# rf-remote.net
KiCad netlist of a schematic drawn in Altium Designer
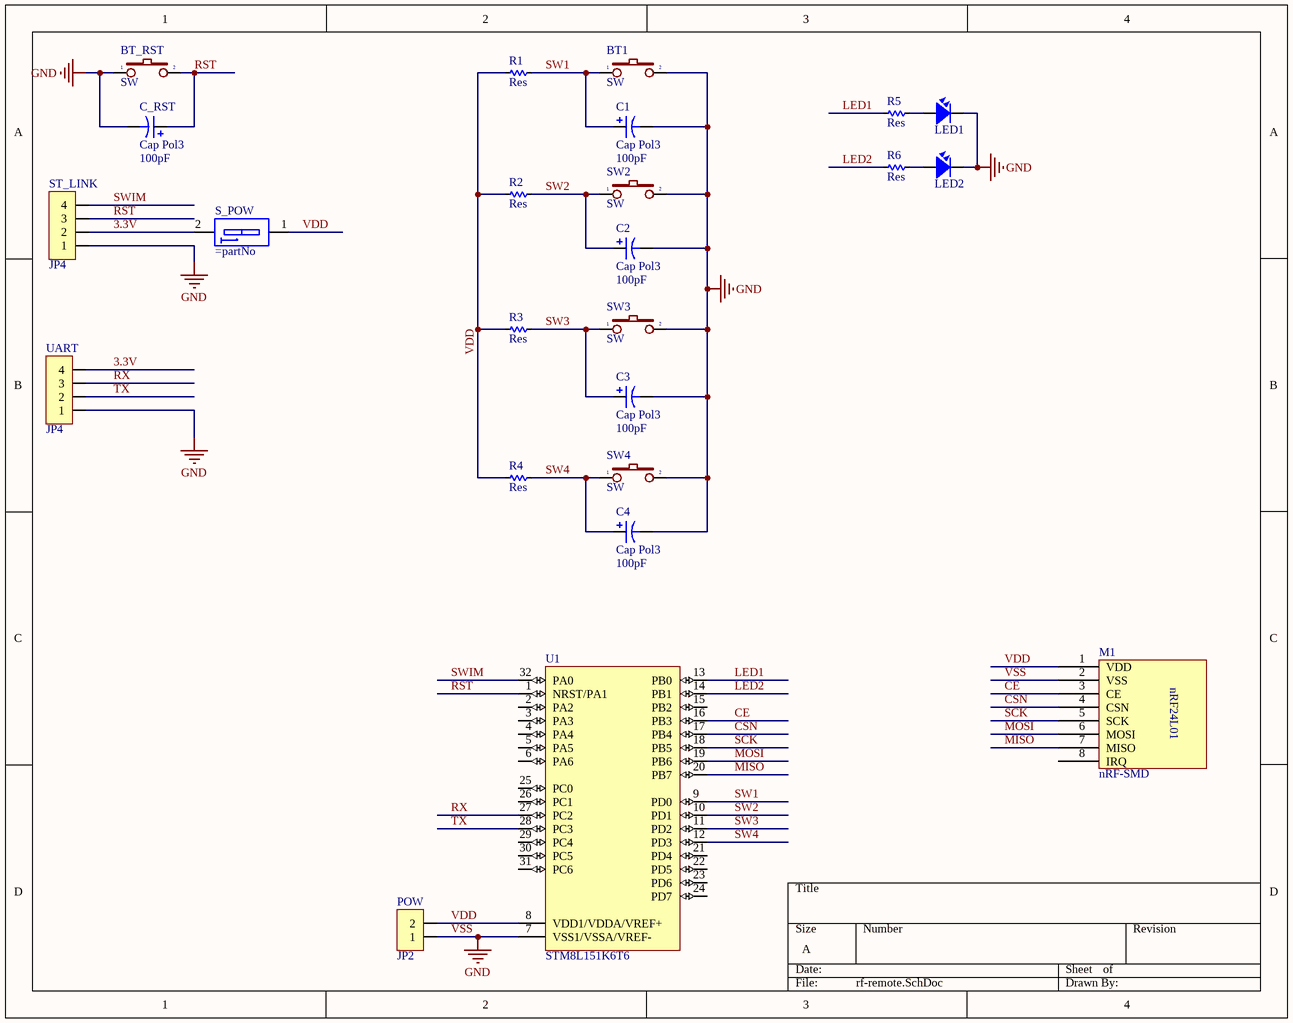
[diagram p0: rf-remote.SchDoc]

(export (version "E")
  (design (tool "Eeschema 10.0.6"))
  (components
    (comp (ref "BT1")
      (value "SW")
      (footprint "SW1-SMD")
      (description "Switch button 2 pin")
      (libsource (lib "LIBRARY") (part "SW2"))
    )
    (comp (ref "BT_RST")
      (value "SW")
      (footprint "SW1-SMD")
      (description "Switch button 2 pin")
      (libsource (lib "LIBRARY") (part "SW2"))
    )
    (comp (ref "C1")
      (value "Cap Pol3")
      (footprint "C0805")
      (description "Polarized Capacitor (Surface Mount)")
      (fields (field (name "ALTIUM_VALUE") "100pF") (field (name "PUBLISHER") "Altium Limited"))
      (libsource (lib "Miscellaneous Devices") (part "Cap Pol3"))
    )
    (comp (ref "C2")
      (value "Cap Pol3")
      (footprint "C0805")
      (description "Polarized Capacitor (Surface Mount)")
      (fields (field (name "ALTIUM_VALUE") "100pF") (field (name "PUBLISHER") "Altium Limited"))
      (libsource (lib "Miscellaneous Devices") (part "Cap Pol3"))
    )
    (comp (ref "C3")
      (value "Cap Pol3")
      (footprint "C0805")
      (description "Polarized Capacitor (Surface Mount)")
      (fields (field (name "ALTIUM_VALUE") "100pF") (field (name "PUBLISHER") "Altium Limited"))
      (libsource (lib "Miscellaneous Devices") (part "Cap Pol3"))
    )
    (comp (ref "C4")
      (value "Cap Pol3")
      (footprint "C0805")
      (description "Polarized Capacitor (Surface Mount)")
      (fields (field (name "ALTIUM_VALUE") "100pF") (field (name "PUBLISHER") "Altium Limited"))
      (libsource (lib "Miscellaneous Devices") (part "Cap Pol3"))
    )
    (comp (ref "C_RST")
      (value "Cap Pol3")
      (footprint "C0805")
      (description "Polarized Capacitor (Surface Mount)")
      (fields (field (name "ALTIUM_VALUE") "100pF") (field (name "PUBLISHER") "Altium Limited"))
      (libsource (lib "Miscellaneous Devices") (part "Cap Pol3"))
    )
    (comp (ref "LED1") (value "LED") (footprint "LED-0805-Blue") (libsource (lib "LIBRARY") (part "LED SMD")))
    (comp (ref "LED2") (value "LED") (footprint "LED-0805-Blue") (libsource (lib "LIBRARY") (part "LED SMD")))
    (comp (ref "M1")
      (value "nRF-SMD")
      (footprint "nRF-SMD")
      (description "MODULE nRF24L01")
      (libsource (lib "My_Library") (part "nRF-SMD"))
    )
    (comp (ref "POW")
      (value "JP2")
      (footprint "JP2-D1T")
      (description "WR-PHD 2.54 mm Angled Socket Header")
      (fields
        (field (name "MANUFACTURER") "Würth Elektronik eiSos GmbH")
        (field (name "PARTNO") "613002143121")
        (field (name "CREATED BY") "Karrer Zheng")
      )
      (libsource (lib "LIBRARY") (part "JP2"))
    )
    (comp (ref "R1")
      (value "Res")
      (footprint "RES-SMD-0805")
      (description "Resistor")
      (fields
        (field (name "MANUFACTURER") "Generic Components")
        (field (name "PUBLISHER") "Altium Hobart Technology Centre")
      )
      (libsource (lib "LIBRARY") (part "Res-SMD"))
    )
    (comp (ref "R2")
      (value "Res")
      (footprint "RES-SMD-0805")
      (description "Resistor")
      (fields
        (field (name "MANUFACTURER") "Generic Components")
        (field (name "PUBLISHER") "Altium Hobart Technology Centre")
      )
      (libsource (lib "LIBRARY") (part "Res-SMD"))
    )
    (comp (ref "R3")
      (value "Res")
      (footprint "RES-SMD-0805")
      (description "Resistor")
      (fields
        (field (name "MANUFACTURER") "Generic Components")
        (field (name "PUBLISHER") "Altium Hobart Technology Centre")
      )
      (libsource (lib "LIBRARY") (part "Res-SMD"))
    )
    (comp (ref "R4")
      (value "Res")
      (footprint "RES-SMD-0805")
      (description "Resistor")
      (fields
        (field (name "MANUFACTURER") "Generic Components")
        (field (name "PUBLISHER") "Altium Hobart Technology Centre")
      )
      (libsource (lib "LIBRARY") (part "Res-SMD"))
    )
    (comp (ref "R5")
      (value "Res")
      (footprint "RES-SMD-0805")
      (description "Resistor")
      (fields
        (field (name "MANUFACTURER") "Generic Components")
        (field (name "PUBLISHER") "Altium Hobart Technology Centre")
      )
      (libsource (lib "LIBRARY") (part "Res-SMD"))
    )
    (comp (ref "R6")
      (value "Res")
      (footprint "RES-SMD-0805")
      (description "Resistor")
      (fields
        (field (name "MANUFACTURER") "Generic Components")
        (field (name "PUBLISHER") "Altium Hobart Technology Centre")
      )
      (libsource (lib "LIBRARY") (part "Res-SMD"))
    )
    (comp (ref "ST_LINK")
      (value "JP4")
      (footprint "JP4-C1T")
      (description "WR-PHD 2.54 mm Angled Socket Header")
      (fields
        (field (name "MANUFACTURER") "Würth Elektronik eiSos GmbH")
        (field (name "PARTNO") "613004143121")
        (field (name "CREATED BY") "Karrer Zheng")
      )
      (libsource (lib "LIBRARY") (part "JP4"))
    )
    (comp (ref "SW2")
      (value "SW")
      (footprint "SW1-SMD")
      (description "Switch button 2 pin")
      (libsource (lib "LIBRARY") (part "SW2"))
    )
    (comp (ref "SW3")
      (value "SW")
      (footprint "SW1-SMD")
      (description "Switch button 2 pin")
      (libsource (lib "LIBRARY") (part "SW2"))
    )
    (comp (ref "SW4")
      (value "SW")
      (footprint "SW1-SMD")
      (description "Switch button 2 pin")
      (libsource (lib "LIBRARY") (part "SW2"))
    )
    (comp (ref "S_POW")
      (value "~")
      (footprint "SW-DIP1-1")
      (description "WS-DITV 2.54 mm small compact THT flat actuator with top tape")
      (fields
        (field (name "MANUFACTURER") "Wurth Elektronik")
        (field (name "PART NO.") "418127160901")
        (field (name "CREATED BY") "Baojun Chen")
      )
      (libsource (lib "LIBRARY") (part "SWDIP1"))
    )
    (comp (ref "U1")
      (value "STM8L151K6T6")
      (footprint "LQFP32_N")
      (libsource (lib "STMicroelectronics STM8L") (part "STM8L151K6T6"))
    )
    (comp (ref "UART")
      (value "JP4")
      (footprint "JP4-C1T")
      (description "WR-PHD 2.54 mm Angled Socket Header")
      (fields
        (field (name "MANUFACTURER") "Würth Elektronik eiSos GmbH")
        (field (name "PARTNO") "613004143121")
        (field (name "CREATED BY") "Karrer Zheng")
      )
      (libsource (lib "LIBRARY") (part "JP4"))
    )
  )
  (nets
    (net (code "1") (name "/3.3V") (class "Default")
      (node (ref "ST_LINK") (pin "2") (pinfunction "2_2") (pintype "passive"))
      (node (ref "S_POW") (pin "2") (pinfunction "2_2") (pintype "passive"))
      (node (ref "UART") (pin "4") (pinfunction "4_4") (pintype "passive"))
    )
    (net (code "2") (name "/CE") (class "Default")
      (node (ref "M1") (pin "3") (pinfunction "CE_3") (pintype "passive"))
      (node (ref "U1") (pin "16") (pinfunction "PB3_16") (pintype "bidirectional"))
    )
    (net (code "3") (name "/CSN") (class "Default")
      (node (ref "M1") (pin "4") (pinfunction "CSN_4") (pintype "passive"))
      (node (ref "U1") (pin "17") (pinfunction "PB4_17") (pintype "bidirectional"))
    )
    (net (code "4") (name "/LED1") (class "Default")
      (node (ref "R5") (pin "2") (pinfunction "2_2") (pintype "passive"))
      (node (ref "U1") (pin "13") (pinfunction "PB0_13") (pintype "bidirectional"))
    )
    (net (code "5") (name "/LED2") (class "Default")
      (node (ref "R6") (pin "2") (pinfunction "2_2") (pintype "passive"))
      (node (ref "U1") (pin "14") (pinfunction "PB1_14") (pintype "bidirectional"))
    )
    (net (code "6") (name "/MISO") (class "Default")
      (node (ref "M1") (pin "7") (pinfunction "MISO_7") (pintype "passive"))
      (node (ref "U1") (pin "20") (pinfunction "PB7_20") (pintype "bidirectional"))
    )
    (net (code "7") (name "/MOSI") (class "Default")
      (node (ref "M1") (pin "6") (pinfunction "MOSI_6") (pintype "passive"))
      (node (ref "U1") (pin "19") (pinfunction "PB6_19") (pintype "bidirectional"))
    )
    (net (code "8") (name "/RST") (class "Default")
      (node (ref "BT_RST") (pin "2") (pinfunction "2_2") (pintype "passive"))
      (node (ref "C_RST") (pin "1") (pinfunction "1_1") (pintype "passive"))
      (node (ref "ST_LINK") (pin "3") (pinfunction "3_3") (pintype "passive"))
      (node (ref "U1") (pin "1") (pinfunction "NRST/PA1_1") (pintype "bidirectional"))
    )
    (net (code "9") (name "/RX") (class "Default")
      (node (ref "U1") (pin "27") (pinfunction "PC2_27") (pintype "bidirectional"))
      (node (ref "UART") (pin "3") (pinfunction "3_3") (pintype "passive"))
    )
    (net (code "10") (name "/SCK") (class "Default")
      (node (ref "M1") (pin "5") (pinfunction "SCK_5") (pintype "passive"))
      (node (ref "U1") (pin "18") (pinfunction "PB5_18") (pintype "bidirectional"))
    )
    (net (code "11") (name "/SW1") (class "Default")
      (node (ref "BT1") (pin "1") (pinfunction "1_1") (pintype "passive"))
      (node (ref "C1") (pin "1") (pinfunction "1_1") (pintype "passive"))
      (node (ref "R1") (pin "1") (pinfunction "1_1") (pintype "passive"))
      (node (ref "U1") (pin "9") (pinfunction "PD0_9") (pintype "bidirectional"))
    )
    (net (code "12") (name "/SW2") (class "Default")
      (node (ref "C2") (pin "1") (pinfunction "1_1") (pintype "passive"))
      (node (ref "R2") (pin "1") (pinfunction "1_1") (pintype "passive"))
      (node (ref "SW2") (pin "1") (pinfunction "1_1") (pintype "passive"))
      (node (ref "U1") (pin "10") (pinfunction "PD1_10") (pintype "bidirectional"))
    )
    (net (code "13") (name "/SW3") (class "Default")
      (node (ref "C3") (pin "1") (pinfunction "1_1") (pintype "passive"))
      (node (ref "R3") (pin "1") (pinfunction "1_1") (pintype "passive"))
      (node (ref "SW3") (pin "1") (pinfunction "1_1") (pintype "passive"))
      (node (ref "U1") (pin "11") (pinfunction "PD2_11") (pintype "bidirectional"))
    )
    (net (code "14") (name "/SW4") (class "Default")
      (node (ref "C4") (pin "1") (pinfunction "1_1") (pintype "passive"))
      (node (ref "R4") (pin "1") (pinfunction "1_1") (pintype "passive"))
      (node (ref "SW4") (pin "1") (pinfunction "1_1") (pintype "passive"))
      (node (ref "U1") (pin "12") (pinfunction "PD3_12") (pintype "bidirectional"))
    )
    (net (code "15") (name "/SWIM") (class "Default")
      (node (ref "ST_LINK") (pin "4") (pinfunction "4_4") (pintype "passive"))
      (node (ref "U1") (pin "32") (pinfunction "PA0_32") (pintype "bidirectional"))
    )
    (net (code "16") (name "/TX") (class "Default")
      (node (ref "U1") (pin "28") (pinfunction "PC3_28") (pintype "bidirectional"))
      (node (ref "UART") (pin "2") (pinfunction "2_2") (pintype "passive"))
    )
    (net (code "17") (name "/VDD") (class "Default")
      (node (ref "M1") (pin "1") (pinfunction "VDD_1") (pintype "passive"))
      (node (ref "POW") (pin "2") (pinfunction "2_2") (pintype "passive"))
      (node (ref "R1") (pin "2") (pinfunction "2_2") (pintype "passive"))
      (node (ref "R2") (pin "2") (pinfunction "2_2") (pintype "passive"))
      (node (ref "R3") (pin "2") (pinfunction "2_2") (pintype "passive"))
      (node (ref "R4") (pin "2") (pinfunction "2_2") (pintype "passive"))
      (node (ref "S_POW") (pin "1") (pinfunction "1_1") (pintype "passive"))
      (node (ref "U1") (pin "8") (pinfunction "VDD1/VDDA/VREF+_8") (pintype "power_in"))
    )
    (net (code "18") (name "GND") (class "Default")
      (node (ref "BT1") (pin "2") (pinfunction "2_2") (pintype "passive"))
      (node (ref "BT_RST") (pin "1") (pinfunction "1_1") (pintype "passive"))
      (node (ref "C1") (pin "2") (pinfunction "2_2") (pintype "passive"))
      (node (ref "C2") (pin "2") (pinfunction "2_2") (pintype "passive"))
      (node (ref "C3") (pin "2") (pinfunction "2_2") (pintype "passive"))
      (node (ref "C4") (pin "2") (pinfunction "2_2") (pintype "passive"))
      (node (ref "C_RST") (pin "2") (pinfunction "2_2") (pintype "passive"))
      (node (ref "LED1") (pin "2") (pinfunction "2_2") (pintype "passive"))
      (node (ref "LED2") (pin "2") (pinfunction "2_2") (pintype "passive"))
      (node (ref "M1") (pin "2") (pinfunction "VSS_2") (pintype "passive"))
      (node (ref "POW") (pin "1") (pinfunction "1_1") (pintype "passive"))
      (node (ref "ST_LINK") (pin "1") (pinfunction "1_1") (pintype "passive"))
      (node (ref "SW2") (pin "2") (pinfunction "2_2") (pintype "passive"))
      (node (ref "SW3") (pin "2") (pinfunction "2_2") (pintype "passive"))
      (node (ref "SW4") (pin "2") (pinfunction "2_2") (pintype "passive"))
      (node (ref "U1") (pin "7") (pinfunction "VSS1/VSSA/VREF-_7") (pintype "power_in"))
      (node (ref "UART") (pin "1") (pinfunction "1_1") (pintype "passive"))
    )
    (net (code "19") (name "Net-(LED1-Pad1)") (class "Default")
      (node (ref "LED1") (pin "1") (pinfunction "1_1") (pintype "passive"))
      (node (ref "R5") (pin "1") (pinfunction "1_1") (pintype "passive"))
    )
    (net (code "20") (name "Net-(LED2-Pad1)") (class "Default")
      (node (ref "LED2") (pin "1") (pinfunction "1_1") (pintype "passive"))
      (node (ref "R6") (pin "1") (pinfunction "1_1") (pintype "passive"))
    )
    (net (code "21") (name "unconnected-(M1-IRQ-Pad8)") (class "Default")
      (node (ref "M1") (pin "8") (pinfunction "IRQ_8") (pintype "passive"))
    )
    (net (code "22") (name "unconnected-(U1-PA2-Pad2)") (class "Default")
      (node (ref "U1") (pin "2") (pinfunction "PA2_2") (pintype "bidirectional"))
    )
    (net (code "23") (name "unconnected-(U1-PA3-Pad3)") (class "Default")
      (node (ref "U1") (pin "3") (pinfunction "PA3_3") (pintype "bidirectional"))
    )
    (net (code "24") (name "unconnected-(U1-PA4-Pad4)") (class "Default")
      (node (ref "U1") (pin "4") (pinfunction "PA4_4") (pintype "bidirectional"))
    )
    (net (code "25") (name "unconnected-(U1-PA5-Pad5)") (class "Default")
      (node (ref "U1") (pin "5") (pinfunction "PA5_5") (pintype "bidirectional"))
    )
    (net (code "26") (name "unconnected-(U1-PA6-Pad6)") (class "Default")
      (node (ref "U1") (pin "6") (pinfunction "PA6_6") (pintype "bidirectional"))
    )
    (net (code "27") (name "unconnected-(U1-PB2-Pad15)") (class "Default")
      (node (ref "U1") (pin "15") (pinfunction "PB2_15") (pintype "bidirectional"))
    )
    (net (code "28") (name "unconnected-(U1-PC0-Pad25)") (class "Default")
      (node (ref "U1") (pin "25") (pinfunction "PC0_25") (pintype "bidirectional"))
    )
    (net (code "29") (name "unconnected-(U1-PC1-Pad26)") (class "Default")
      (node (ref "U1") (pin "26") (pinfunction "PC1_26") (pintype "bidirectional"))
    )
    (net (code "30") (name "unconnected-(U1-PC4-Pad29)") (class "Default")
      (node (ref "U1") (pin "29") (pinfunction "PC4_29") (pintype "bidirectional"))
    )
    (net (code "31") (name "unconnected-(U1-PC5-Pad30)") (class "Default")
      (node (ref "U1") (pin "30") (pinfunction "PC5_30") (pintype "bidirectional"))
    )
    (net (code "32") (name "unconnected-(U1-PC6-Pad31)") (class "Default")
      (node (ref "U1") (pin "31") (pinfunction "PC6_31") (pintype "bidirectional"))
    )
    (net (code "33") (name "unconnected-(U1-PD4-Pad21)") (class "Default")
      (node (ref "U1") (pin "21") (pinfunction "PD4_21") (pintype "bidirectional"))
    )
    (net (code "34") (name "unconnected-(U1-PD5-Pad22)") (class "Default")
      (node (ref "U1") (pin "22") (pinfunction "PD5_22") (pintype "bidirectional"))
    )
    (net (code "35") (name "unconnected-(U1-PD6-Pad23)") (class "Default")
      (node (ref "U1") (pin "23") (pinfunction "PD6_23") (pintype "bidirectional"))
    )
    (net (code "36") (name "unconnected-(U1-PD7-Pad24)") (class "Default")
      (node (ref "U1") (pin "24") (pinfunction "PD7_24") (pintype "bidirectional"))
    )
  )
)
